# SCH_Pro.net
KiCad netlist of a schematic drawn in Altium Designer
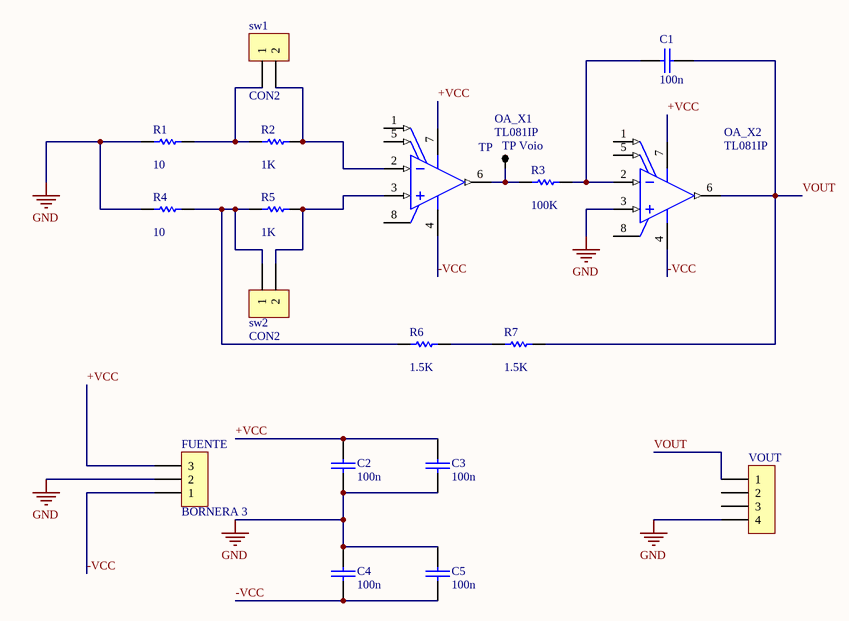
[diagram p0: SCH_Pro.SchDoc]

(export (version "E")
  (design (tool "Eeschema 10.0.6"))
  (components
    (comp (ref "C1") (value "100n") (footprint "CAP200") (libsource (lib "LIB PIO IX") (part "CAP")))
    (comp (ref "C2") (value "100n") (footprint "CAP200") (libsource (lib "LIBEBAL") (part "CAP")))
    (comp (ref "C3") (value "100n") (footprint "CAP100") (libsource (lib "LIBEBAL") (part "CAP")))
    (comp (ref "C4") (value "100n") (footprint "CAP100") (libsource (lib "LIBEBAL") (part "CAP")))
    (comp (ref "C5") (value "100n") (footprint "CAP100") (libsource (lib "LIBEBAL") (part "CAP")))
    (comp (ref "FUENTE")
      (value "BORNERA 3")
      (footprint "BORNERA3")
      (libsource (lib "LIBEBAL") (part "BORNERA 3"))
    )
    (comp (ref "OA_X1")
      (value "TL081IP")
      (footprint "TI-P8")
      (description "JFET-Input Operational Amplifier, 7 to 36 V, -40 to 85 degC, 8-pin DIP (P8), Pb-Free (RoHS)")
      (fields (field (name "MANUFACTURER") "Texas Instruments"))
      (libsource (lib "TI Amplifiers and Linear Operational Amplifier General Purpose") (part "TL081IP"))
    )
    (comp (ref "OA_X2")
      (value "TL081IP")
      (footprint "TI-P8")
      (description "JFET-Input Operational Amplifier, 7 to 36 V, -40 to 85 degC, 8-pin DIP (P8), Pb-Free (RoHS)")
      (fields (field (name "MANUFACTURER") "Texas Instruments"))
      (libsource (lib "TI Amplifiers and Linear Operational Amplifier General Purpose") (part "TL081IP"))
    )
    (comp (ref "R1")
      (value "10")
      (footprint "AXIAL-0.3")
      (description "Resistor")
      (fields (field (name "PUBLISHER") "Altium Limited"))
      (libsource (lib "Miscellaneous Devices") (part "Res1"))
    )
    (comp (ref "R2")
      (value "1K")
      (footprint "AXIAL-0.3")
      (description "Resistor")
      (fields (field (name "PUBLISHER") "Altium Limited"))
      (libsource (lib "Miscellaneous Devices") (part "Res1"))
    )
    (comp (ref "R3")
      (value "100K")
      (footprint "AXIAL-0.3")
      (description "Resistor")
      (fields (field (name "PUBLISHER") "Altium Limited"))
      (libsource (lib "Miscellaneous Devices") (part "Res1"))
    )
    (comp (ref "R4")
      (value "10")
      (footprint "AXIAL-0.3")
      (description "Resistor")
      (fields (field (name "PUBLISHER") "Altium Limited"))
      (libsource (lib "Miscellaneous Devices") (part "Res1"))
    )
    (comp (ref "R5")
      (value "1K")
      (footprint "AXIAL-0.3")
      (description "Resistor")
      (fields (field (name "PUBLISHER") "Altium Limited"))
      (libsource (lib "Miscellaneous Devices") (part "Res1"))
    )
    (comp (ref "R6")
      (value "1.5K")
      (footprint "AXIAL-0.3")
      (description "Resistor")
      (fields (field (name "PUBLISHER") "Altium Limited"))
      (libsource (lib "Miscellaneous Devices") (part "Res1"))
    )
    (comp (ref "R7")
      (value "1.5K")
      (footprint "AXIAL-0.3")
      (description "Resistor")
      (fields (field (name "PUBLISHER") "Altium Limited"))
      (libsource (lib "Miscellaneous Devices") (part "Res1"))
    )
    (comp (ref "sw1") (value "CON2") (footprint "SIP2") (libsource (lib "LIBEBAL") (part "CON2")))
    (comp (ref "sw2") (value "CON2") (footprint "SIP2") (libsource (lib "") (part "CON2_1")))
    (comp (ref "TP Voio") (value "TP") (footprint "TPTH") (libsource (lib "LIBEBAL") (part "TP")))
    (comp (ref "VOUT") (value "~") (footprint "SIP4") (libsource (lib "LIBEBAL") (part "CON4")))
  )
  (nets
    (net (code "1") (name "/+VCC") (class "Default")
      (node (ref "C2") (pin "1") (pinfunction "1_1") (pintype "passive"))
      (node (ref "C3") (pin "1") (pinfunction "1_1") (pintype "passive"))
      (node (ref "FUENTE") (pin "3") (pinfunction "3_3") (pintype "passive"))
      (node (ref "OA_X1") (pin "7") (pinfunction "VCC+_7") (pintype "power_in"))
      (node (ref "OA_X2") (pin "7") (pinfunction "VCC+_7") (pintype "power_in"))
    )
    (net (code "2") (name "/-VCC") (class "Default")
      (node (ref "C4") (pin "2") (pinfunction "2_2") (pintype "passive"))
      (node (ref "C5") (pin "2") (pinfunction "2_2") (pintype "passive"))
      (node (ref "FUENTE") (pin "1") (pinfunction "1_1") (pintype "passive"))
      (node (ref "OA_X1") (pin "4") (pinfunction "VCC-_4") (pintype "power_in"))
      (node (ref "OA_X2") (pin "4") (pinfunction "VCC-_4") (pintype "power_in"))
    )
    (net (code "3") (name "/VOUT") (class "Default")
      (node (ref "C1") (pin "2") (pinfunction "2_2") (pintype "passive"))
      (node (ref "OA_X2") (pin "6") (pinfunction "OUT_6") (pintype "output"))
      (node (ref "R7") (pin "2") (pinfunction "2_2") (pintype "passive"))
      (node (ref "VOUT") (pin "1") (pinfunction "1_1") (pintype "passive"))
    )
    (net (code "4") (name "GND") (class "Default")
      (node (ref "C2") (pin "2") (pinfunction "2_2") (pintype "passive"))
      (node (ref "C3") (pin "2") (pinfunction "2_2") (pintype "passive"))
      (node (ref "C4") (pin "1") (pinfunction "1_1") (pintype "passive"))
      (node (ref "C5") (pin "1") (pinfunction "1_1") (pintype "passive"))
      (node (ref "FUENTE") (pin "2") (pinfunction "2_2") (pintype "passive"))
      (node (ref "OA_X2") (pin "3") (pinfunction "IN+_3") (pintype "input"))
      (node (ref "R1") (pin "1") (pinfunction "1_1") (pintype "passive"))
      (node (ref "R4") (pin "1") (pinfunction "1_1") (pintype "passive"))
      (node (ref "VOUT") (pin "4") (pinfunction "4_4") (pintype "passive"))
    )
    (net (code "5") (name "Net-(OA_X1-IN+)") (class "Default")
      (node (ref "OA_X1") (pin "3") (pinfunction "IN+_3") (pintype "input"))
      (node (ref "R5") (pin "2") (pinfunction "2_2") (pintype "passive"))
      (node (ref "sw2") (pin "2") (pinfunction "2_2") (pintype "passive"))
    )
    (net (code "6") (name "Net-(OA_X1-IN-)") (class "Default")
      (node (ref "OA_X1") (pin "2") (pinfunction "IN-_2") (pintype "input"))
      (node (ref "R2") (pin "2") (pinfunction "2_2") (pintype "passive"))
      (node (ref "sw1") (pin "2") (pinfunction "2_2") (pintype "passive"))
    )
    (net (code "7") (name "Net-(OA_X1-OUT)") (class "Default")
      (node (ref "OA_X1") (pin "6") (pinfunction "OUT_6") (pintype "output"))
      (node (ref "R3") (pin "1") (pinfunction "1_1") (pintype "passive"))
      (node (ref "TP Voio") (pin "1") (pinfunction "1_1") (pintype "passive"))
    )
    (net (code "8") (name "Net-(OA_X2-IN-)") (class "Default")
      (node (ref "C1") (pin "1") (pinfunction "1_1") (pintype "passive"))
      (node (ref "OA_X2") (pin "2") (pinfunction "IN-_2") (pintype "input"))
      (node (ref "R3") (pin "2") (pinfunction "2_2") (pintype "passive"))
    )
    (net (code "9") (name "Net-(R1-Pad2)") (class "Default")
      (node (ref "R1") (pin "2") (pinfunction "2_2") (pintype "passive"))
      (node (ref "R2") (pin "1") (pinfunction "1_1") (pintype "passive"))
      (node (ref "sw1") (pin "1") (pinfunction "1_1") (pintype "passive"))
    )
    (net (code "10") (name "Net-(R4-Pad2)") (class "Default")
      (node (ref "R4") (pin "2") (pinfunction "2_2") (pintype "passive"))
      (node (ref "R5") (pin "1") (pinfunction "1_1") (pintype "passive"))
      (node (ref "R6") (pin "1") (pinfunction "1_1") (pintype "passive"))
      (node (ref "sw2") (pin "1") (pinfunction "1_1") (pintype "passive"))
    )
    (net (code "11") (name "Net-(R6-Pad2)") (class "Default")
      (node (ref "R6") (pin "2") (pinfunction "2_2") (pintype "passive"))
      (node (ref "R7") (pin "1") (pinfunction "1_1") (pintype "passive"))
    )
    (net (code "12") (name "unconnected-(OA_X1-NC-Pad8)") (class "Default")
      (node (ref "OA_X1") (pin "8") (pinfunction "NC_8") (pintype "passive"))
    )
    (net (code "13") (name "unconnected-(OA_X1-OFFSET_N1-Pad1)") (class "Default")
      (node (ref "OA_X1") (pin "1") (pinfunction "OFFSET_N1_1") (pintype "input"))
    )
    (net (code "14") (name "unconnected-(OA_X1-OFFSET_N2-Pad5)") (class "Default")
      (node (ref "OA_X1") (pin "5") (pinfunction "OFFSET_N2_5") (pintype "input"))
    )
    (net (code "15") (name "unconnected-(OA_X2-NC-Pad8)") (class "Default")
      (node (ref "OA_X2") (pin "8") (pinfunction "NC_8") (pintype "passive"))
    )
    (net (code "16") (name "unconnected-(OA_X2-OFFSET_N1-Pad1)") (class "Default")
      (node (ref "OA_X2") (pin "1") (pinfunction "OFFSET_N1_1") (pintype "input"))
    )
    (net (code "17") (name "unconnected-(OA_X2-OFFSET_N2-Pad5)") (class "Default")
      (node (ref "OA_X2") (pin "5") (pinfunction "OFFSET_N2_5") (pintype "input"))
    )
    (net (code "18") (name "unconnected-(VOUT-Pad2)") (class "Default")
      (node (ref "VOUT") (pin "2") (pinfunction "2_2") (pintype "passive"))
    )
    (net (code "19") (name "unconnected-(VOUT-Pad3)") (class "Default")
      (node (ref "VOUT") (pin "3") (pinfunction "3_3") (pintype "passive"))
    )
  )
)
